# PWR_BRGwFilter.net
KiCad netlist of a schematic drawn in Altium Designer
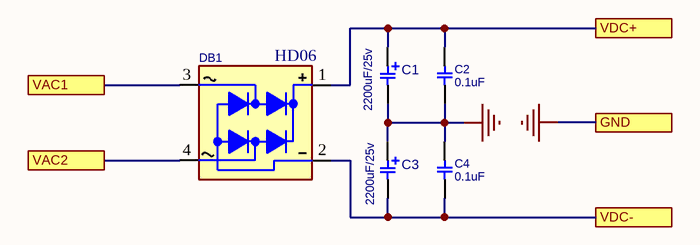
[diagram p0: PWR_BRGwFilter.SchDoc]

(export (version "E")
  (design (tool "Eeschema 10.0.6"))
  (components
    (comp (ref "C1")
      (value "2200uF/25v")
      (footprint "C_EL_12X25")
      (description "CAP, THD, ELEC,")
      (fields (field (name "MANF_P#") "MANF_PART#") (field (name "MANF") "MANF"))
      (libsource (lib "passive_thd") (part "CAP_THD_EL_12X25"))
    )
    (comp (ref "C2")
      (value "0.1uF")
      (footprint "C0603")
      (description "CAP, MLCC, -F, -V, MATERIAL, -%, 0201")
      (fields (field (name "MANF_P#") "MANF_PART#"))
      (libsource (lib "passive_smd") (part "CAP_SMD_MLCC_0805"))
    )
    (comp (ref "C3")
      (value "2200uF/25v")
      (footprint "C_EL_12X25")
      (description "CAP, THD, ELEC,")
      (fields (field (name "MANF_P#") "MANF_PART#") (field (name "MANF") "MANF"))
      (libsource (lib "passive_thd") (part "CAP_THD_EL_12X25"))
    )
    (comp (ref "C4")
      (value "0.1uF")
      (footprint "C0603")
      (description "CAP, MLCC, -F, -V, MATERIAL, -%, 0201")
      (fields (field (name "MANF_P#") "MANF_PART#"))
      (libsource (lib "passive_smd") (part "CAP_SMD_MLCC_0805"))
    )
    (comp (ref "DB1")
      (value "HD06")
      (footprint "DBRG_DIPSMD_MINI")
      (description "DIODE, BRIDGE,")
      (libsource (lib "diode") (part "DIODE_SMD_BRIDGE_HD06"))
    )
  )
  (nets
    (net (code "1") (name "/VAC1") (class "Default")
      (node (ref "DB1") (pin "3") (pinfunction "ACIN2_3") (pintype "passive"))
    )
    (net (code "2") (name "/VAC2") (class "Default")
      (node (ref "DB1") (pin "4") (pinfunction "ACIN1_4") (pintype "passive"))
    )
    (net (code "3") (name "/VDC+") (class "Default")
      (node (ref "C1") (pin "1") (pinfunction "1_1") (pintype "passive"))
      (node (ref "C2") (pin "2") (pinfunction "2_2") (pintype "passive"))
      (node (ref "DB1") (pin "1") (pinfunction "DCOUT+_1") (pintype "passive"))
    )
    (net (code "4") (name "/VDC-") (class "Default")
      (node (ref "C3") (pin "2") (pinfunction "2_2") (pintype "passive"))
      (node (ref "C4") (pin "1") (pinfunction "1_1") (pintype "passive"))
      (node (ref "DB1") (pin "2") (pinfunction "DCOUT-_2") (pintype "passive"))
    )
    (net (code "5") (name "GND") (class "Default")
      (node (ref "C1") (pin "2") (pinfunction "2_2") (pintype "passive"))
      (node (ref "C2") (pin "1") (pinfunction "1_1") (pintype "passive"))
      (node (ref "C3") (pin "1") (pinfunction "1_1") (pintype "passive"))
      (node (ref "C4") (pin "2") (pinfunction "2_2") (pintype "passive"))
    )
  )
)
